# OctoWatchScheme2.net
KiCad netlist of a schematic drawn in EAGLE
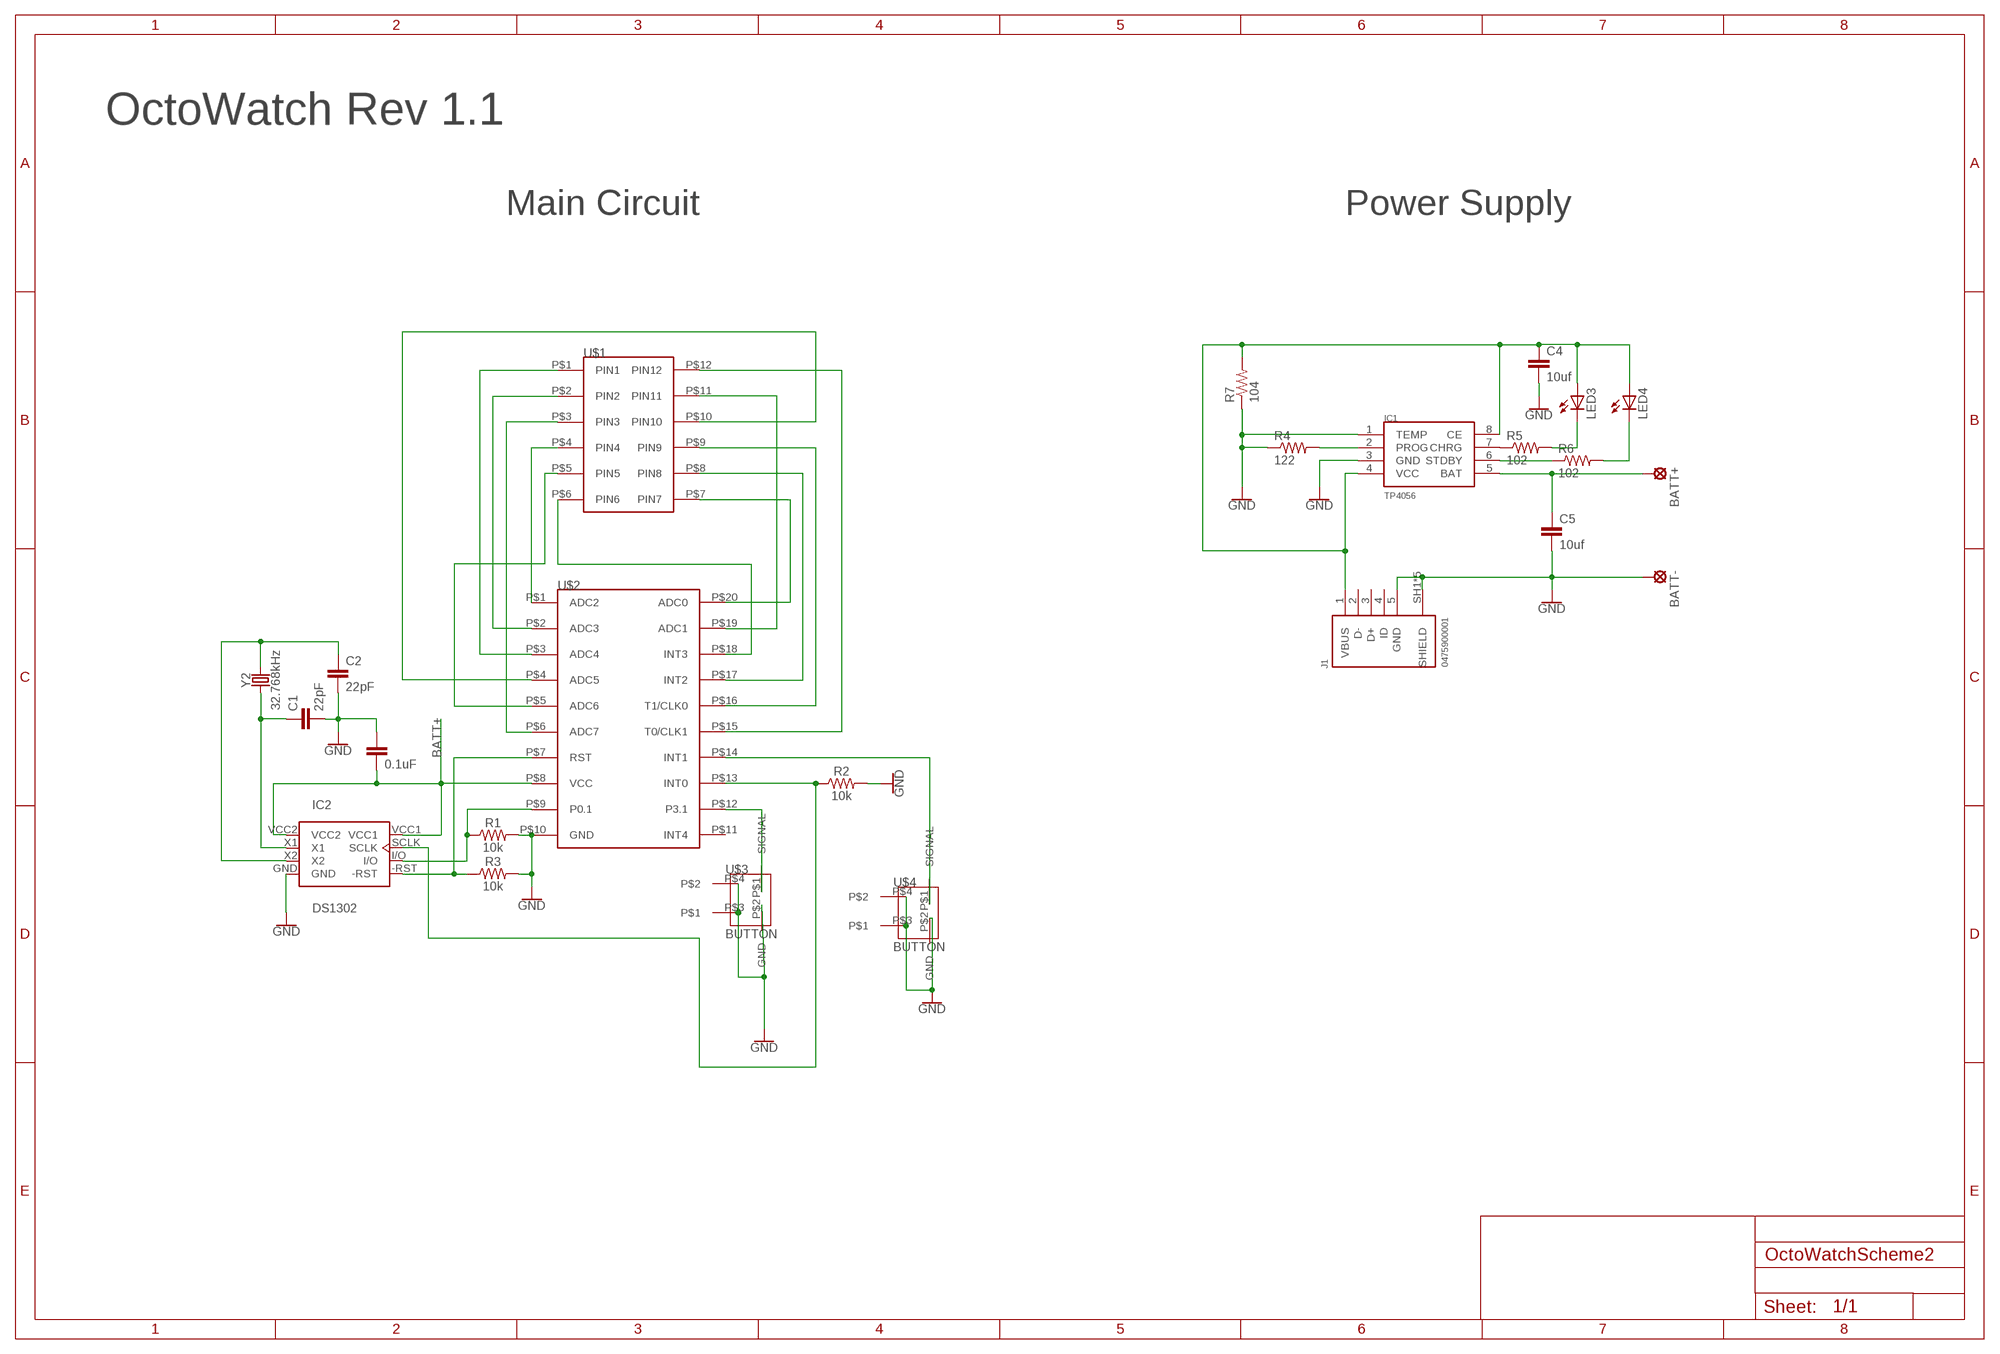
[diagram p0: schematic, sheet 1]

(export (version "E")
  (design (tool "Eeschema 10.0.6"))
  (components
    (comp (ref "BATT+")
      (value "LSP13")
      (footprint "eagle-import:LSP13")
      (libsource (lib "eagle-import") (part "LSP13"))
    )
    (comp (ref "BATT-")
      (value "LSP13")
      (footprint "eagle-import:LSP13")
      (libsource (lib "eagle-import") (part "LSP13"))
    )
    (comp (ref "C1")
      (value "22pF")
      (footprint "eagle-import:0402-TIGHT")
      (libsource (lib "eagle-import") (part "22PF-0402T-16V-10%"))
    )
    (comp (ref "C2")
      (value "22pF")
      (footprint "eagle-import:0402-TIGHT")
      (libsource (lib "eagle-import") (part "22PF-0402T-16V-10%"))
    )
    (comp (ref "C3")
      (value "0.1uF")
      (footprint "eagle-import:0402")
      (libsource (lib "eagle-import") (part "0.1UF-0402-6.3V-10%-X7R"))
    )
    (comp (ref "C4")
      (value "10uf")
      (footprint "eagle-import:C0805")
      (libsource (lib "eagle-import") (part "C-EUC0805"))
    )
    (comp (ref "C5")
      (value "10uf")
      (footprint "eagle-import:C0805")
      (libsource (lib "eagle-import") (part "C-EUC0805"))
    )
    (comp (ref "IC1")
      (value "TP4056")
      (footprint "eagle-import:SOP-8")
      (libsource (lib "eagle-import") (part "TP4056"))
    )
    (comp (ref "IC2")
      (value "DS1302")
      (footprint "eagle-import:DIL08")
      (libsource (lib "eagle-import") (part "DS1302"))
    )
    (comp (ref "J1")
      (value "0475900001")
      (footprint "eagle-import:0475900001")
      (fields
        (field (name "DIGIKEY_PARTNO") "WM17144TR-ND")
        (field (name "MANUFACTURER") "Molex")
        (field (name "CREATED_BY") "PCBLayout.com")
      )
      (libsource (lib "eagle-import") (part "0475900001"))
    )
    (comp (ref "LED3")
      (value "LEDCHIPLED_0603")
      (footprint "eagle-import:CHIPLED_0603")
      (libsource (lib "eagle-import") (part "LEDCHIPLED_0603"))
    )
    (comp (ref "LED4")
      (value "LEDCHIPLED_0603")
      (footprint "eagle-import:CHIPLED_0603")
      (libsource (lib "eagle-import") (part "LEDCHIPLED_0603"))
    )
    (comp (ref "R1")
      (value "10k")
      (footprint "eagle-import:0603")
      (libsource (lib "eagle-import") (part "10KOHM-0603-1/10W-1%"))
    )
    (comp (ref "R2")
      (value "10k")
      (footprint "eagle-import:0603")
      (libsource (lib "eagle-import") (part "10KOHM-0603-1/10W-1%"))
    )
    (comp (ref "R3")
      (value "10k")
      (footprint "eagle-import:0603")
      (libsource (lib "eagle-import") (part "10KOHM-0603-1/10W-1%"))
    )
    (comp (ref "R4")
      (value "122")
      (footprint "eagle-import:R0402")
      (libsource (lib "eagle-import") (part "rcl_334_R-US_R0402"))
    )
    (comp (ref "R5")
      (value "102")
      (footprint "eagle-import:R0402")
      (libsource (lib "eagle-import") (part "rcl_334_R-US_R0402"))
    )
    (comp (ref "R6")
      (value "102")
      (footprint "eagle-import:R0402")
      (libsource (lib "eagle-import") (part "rcl_334_R-US_R0402"))
    )
    (comp (ref "R7")
      (value "104")
      (footprint "eagle-import:R0805")
      (libsource (lib "eagle-import") (part "R-US_R0805"))
    )
    (comp (ref "U$1")
      (value "LED_SEGMENT")
      (footprint "eagle-import:LED_SEGMENT")
      (libsource (lib "eagle-import") (part "LED_SEGMENT"))
    )
    (comp (ref "U$2")
      (value "STC15F204AE")
      (footprint "eagle-import:STC15F204AE")
      (libsource (lib "eagle-import") (part "STC15F204AE"))
    )
    (comp (ref "U$3")
      (value "BUTTON")
      (footprint "eagle-import:BUTTON")
      (libsource (lib "eagle-import") (part "BUTTON"))
    )
    (comp (ref "U$4")
      (value "BUTTON")
      (footprint "eagle-import:BUTTON")
      (libsource (lib "eagle-import") (part "BUTTON"))
    )
    (comp (ref "Y2")
      (value "32.768kHz")
      (footprint "eagle-import:CRYSTAL-PTH-2X6-CYL")
      (libsource (lib "eagle-import") (part "CRYSTAL-32.768KHZPTH-2X6"))
    )
  )
  (nets
    (net (code "1") (name "/BATT+") (class "Default")
      (node (ref "C3") (pin "2") (pinfunction "2_2") (pintype "passive"))
      (node (ref "IC2") (pin "VCC1") (pinfunction "VCC1_VCC1") (pintype "power_in"))
      (node (ref "IC2") (pin "VCC2") (pinfunction "VCC2_VCC2") (pintype "power_in"))
      (node (ref "U$2") (pin "P$8") (pinfunction "VCC_P$8") (pintype "bidirectional"))
    )
    (net (code "2") (name "GND") (class "Default")
      (node (ref "BATT-") (pin "MP") (pinfunction "MP_MP") (pintype "passive"))
      (node (ref "C1") (pin "2") (pinfunction "2_2") (pintype "passive"))
      (node (ref "C2") (pin "2") (pinfunction "2_2") (pintype "passive"))
      (node (ref "C3") (pin "1") (pinfunction "1_1") (pintype "passive"))
      (node (ref "C4") (pin "2") (pinfunction "2_2") (pintype "passive"))
      (node (ref "C5") (pin "2") (pinfunction "2_2") (pintype "passive"))
      (node (ref "IC1") (pin "1") (pinfunction "TEMP_1") (pintype "bidirectional"))
      (node (ref "IC1") (pin "3") (pinfunction "GND_3") (pintype "bidirectional"))
      (node (ref "IC2") (pin "GND") (pinfunction "GND_GND") (pintype "passive"))
      (node (ref "J1") (pin "5") (pinfunction "GND_5") (pintype "passive"))
      (node (ref "J1") (pin "SH1") (pinfunction "SHIELD_SH1") (pintype "power_in"))
      (node (ref "J1") (pin "SH2") (pinfunction "SHIELD_SH2") (pintype "power_in"))
      (node (ref "J1") (pin "SH3") (pinfunction "SHIELD_SH3") (pintype "power_in"))
      (node (ref "J1") (pin "SH4") (pinfunction "SHIELD_SH4") (pintype "power_in"))
      (node (ref "J1") (pin "SH5") (pinfunction "SHIELD_SH5") (pintype "power_in"))
      (node (ref "R1") (pin "2") (pinfunction "2_2") (pintype "passive"))
      (node (ref "R2") (pin "2") (pinfunction "2_2") (pintype "passive"))
      (node (ref "R3") (pin "2") (pinfunction "2_2") (pintype "passive"))
      (node (ref "R4") (pin "1") (pinfunction "1_1") (pintype "passive"))
      (node (ref "R7") (pin "1") (pinfunction "1_1") (pintype "passive"))
      (node (ref "U$2") (pin "P$10") (pinfunction "GND_P$10") (pintype "bidirectional"))
      (node (ref "U$3") (pin "P$2") (pinfunction "GND_P$2") (pintype "bidirectional"))
      (node (ref "U$3") (pin "P$3") (pinfunction "P$1_P$3") (pintype "bidirectional"))
      (node (ref "U$3") (pin "P$4") (pinfunction "P$2_P$4") (pintype "bidirectional"))
      (node (ref "U$4") (pin "P$2") (pinfunction "GND_P$2") (pintype "bidirectional"))
      (node (ref "U$4") (pin "P$3") (pinfunction "P$1_P$3") (pintype "bidirectional"))
      (node (ref "U$4") (pin "P$4") (pinfunction "P$2_P$4") (pintype "bidirectional"))
    )
    (net (code "3") (name "Net-(C1-Pad1)") (class "Default")
      (node (ref "C1") (pin "1") (pinfunction "1_1") (pintype "passive"))
      (node (ref "IC2") (pin "X1") (pinfunction "X1_X1") (pintype "tri_state"))
      (node (ref "Y2") (pin "1") (pinfunction "1_1") (pintype "passive"))
    )
    (net (code "4") (name "Net-(C2-Pad1)") (class "Default")
      (node (ref "C2") (pin "1") (pinfunction "1_1") (pintype "passive"))
      (node (ref "IC2") (pin "X2") (pinfunction "X2_X2") (pintype "tri_state"))
      (node (ref "Y2") (pin "2") (pinfunction "2_2") (pintype "passive"))
    )
    (net (code "5") (name "Net-(IC1-BAT)") (class "Default")
      (node (ref "BATT+") (pin "MP") (pinfunction "MP_MP") (pintype "passive"))
      (node (ref "C5") (pin "1") (pinfunction "1_1") (pintype "passive"))
      (node (ref "IC1") (pin "5") (pinfunction "BAT_5") (pintype "bidirectional"))
    )
    (net (code "6") (name "Net-(IC1-CE)") (class "Default")
      (node (ref "C4") (pin "1") (pinfunction "1_1") (pintype "passive"))
      (node (ref "IC1") (pin "4") (pinfunction "VCC_4") (pintype "bidirectional"))
      (node (ref "IC1") (pin "8") (pinfunction "CE_8") (pintype "bidirectional"))
      (node (ref "J1") (pin "1") (pinfunction "VBUS_1") (pintype "passive"))
      (node (ref "LED3") (pin "A") (pinfunction "A_A") (pintype "passive"))
      (node (ref "LED4") (pin "A") (pinfunction "A_A") (pintype "passive"))
      (node (ref "R7") (pin "2") (pinfunction "2_2") (pintype "passive"))
    )
    (net (code "7") (name "Net-(IC1-CHRG)") (class "Default")
      (node (ref "IC1") (pin "7") (pinfunction "CHRG_7") (pintype "bidirectional"))
      (node (ref "R5") (pin "1") (pinfunction "1_1") (pintype "passive"))
    )
    (net (code "8") (name "Net-(IC1-PROG)") (class "Default")
      (node (ref "IC1") (pin "2") (pinfunction "PROG_2") (pintype "bidirectional"))
      (node (ref "R4") (pin "2") (pinfunction "2_2") (pintype "passive"))
    )
    (net (code "9") (name "Net-(IC1-STDBY)") (class "Default")
      (node (ref "IC1") (pin "6") (pinfunction "STDBY_6") (pintype "bidirectional"))
      (node (ref "R6") (pin "1") (pinfunction "1_1") (pintype "passive"))
    )
    (net (code "10") (name "Net-(LED3-PadC)") (class "Default")
      (node (ref "LED3") (pin "C") (pinfunction "C_C") (pintype "passive"))
      (node (ref "R5") (pin "2") (pinfunction "2_2") (pintype "passive"))
    )
    (net (code "11") (name "Net-(LED4-PadC)") (class "Default")
      (node (ref "LED4") (pin "C") (pinfunction "C_C") (pintype "passive"))
      (node (ref "R6") (pin "2") (pinfunction "2_2") (pintype "passive"))
    )
    (net (code "12") (name "Net-(U$1-PIN1)") (class "Default")
      (node (ref "U$1") (pin "P$1") (pinfunction "PIN1_P$1") (pintype "bidirectional"))
      (node (ref "U$2") (pin "P$3") (pinfunction "ADC4_P$3") (pintype "bidirectional"))
    )
    (net (code "13") (name "Net-(U$1-PIN2)") (class "Default")
      (node (ref "U$1") (pin "P$2") (pinfunction "PIN2_P$2") (pintype "bidirectional"))
      (node (ref "U$2") (pin "P$2") (pinfunction "ADC3_P$2") (pintype "bidirectional"))
    )
    (net (code "14") (name "Net-(U$1-PIN3)") (class "Default")
      (node (ref "U$1") (pin "P$3") (pinfunction "PIN3_P$3") (pintype "bidirectional"))
      (node (ref "U$2") (pin "P$6") (pinfunction "ADC7_P$6") (pintype "bidirectional"))
    )
    (net (code "15") (name "Net-(U$1-PIN4)") (class "Default")
      (node (ref "U$1") (pin "P$4") (pinfunction "PIN4_P$4") (pintype "bidirectional"))
      (node (ref "U$2") (pin "P$1") (pinfunction "ADC2_P$1") (pintype "bidirectional"))
    )
    (net (code "16") (name "Net-(U$1-PIN5)") (class "Default")
      (node (ref "U$1") (pin "P$5") (pinfunction "PIN5_P$5") (pintype "bidirectional"))
      (node (ref "U$2") (pin "P$5") (pinfunction "ADC6_P$5") (pintype "bidirectional"))
    )
    (net (code "17") (name "Net-(U$1-PIN6)") (class "Default")
      (node (ref "U$1") (pin "P$6") (pinfunction "PIN6_P$6") (pintype "bidirectional"))
      (node (ref "U$2") (pin "P$18") (pinfunction "INT3_P$18") (pintype "bidirectional"))
    )
    (net (code "18") (name "Net-(U$1-PIN7)") (class "Default")
      (node (ref "U$1") (pin "P$7") (pinfunction "PIN7_P$7") (pintype "bidirectional"))
      (node (ref "U$2") (pin "P$20") (pinfunction "ADC0_P$20") (pintype "bidirectional"))
    )
    (net (code "19") (name "Net-(U$1-PIN8)") (class "Default")
      (node (ref "U$1") (pin "P$8") (pinfunction "PIN8_P$8") (pintype "bidirectional"))
      (node (ref "U$2") (pin "P$17") (pinfunction "INT2_P$17") (pintype "bidirectional"))
    )
    (net (code "20") (name "Net-(U$1-PIN9)") (class "Default")
      (node (ref "U$1") (pin "P$9") (pinfunction "PIN9_P$9") (pintype "bidirectional"))
      (node (ref "U$2") (pin "P$16") (pinfunction "T1/CLK0_P$16") (pintype "bidirectional"))
    )
    (net (code "21") (name "Net-(U$1-PIN10)") (class "Default")
      (node (ref "U$1") (pin "P$10") (pinfunction "PIN10_P$10") (pintype "bidirectional"))
      (node (ref "U$2") (pin "P$4") (pinfunction "ADC5_P$4") (pintype "bidirectional"))
    )
    (net (code "22") (name "Net-(U$1-PIN11)") (class "Default")
      (node (ref "U$1") (pin "P$11") (pinfunction "PIN11_P$11") (pintype "bidirectional"))
      (node (ref "U$2") (pin "P$19") (pinfunction "ADC1_P$19") (pintype "bidirectional"))
    )
    (net (code "23") (name "Net-(U$1-PIN12)") (class "Default")
      (node (ref "U$1") (pin "P$12") (pinfunction "PIN12_P$12") (pintype "bidirectional"))
      (node (ref "U$2") (pin "P$15") (pinfunction "T0/CLK1_P$15") (pintype "bidirectional"))
    )
    (net (code "24") (name "Net-(U$2-INT0)") (class "Default")
      (node (ref "IC2") (pin "SCLK") (pinfunction "SCLK_SCLK") (pintype "tri_state"))
      (node (ref "R2") (pin "1") (pinfunction "1_1") (pintype "passive"))
      (node (ref "U$2") (pin "P$13") (pinfunction "INT0_P$13") (pintype "bidirectional"))
    )
    (net (code "25") (name "Net-(U$2-INT1)") (class "Default")
      (node (ref "U$2") (pin "P$14") (pinfunction "INT1_P$14") (pintype "bidirectional"))
      (node (ref "U$4") (pin "P$1") (pinfunction "SIGNAL_P$1") (pintype "bidirectional"))
    )
    (net (code "26") (name "Net-(U$2-P0.1)") (class "Default")
      (node (ref "IC2") (pin "I/O") (pinfunction "I/O_I/O") (pintype "bidirectional"))
      (node (ref "R1") (pin "1") (pinfunction "1_1") (pintype "passive"))
      (node (ref "U$2") (pin "P$9") (pinfunction "P0.1_P$9") (pintype "bidirectional"))
    )
    (net (code "27") (name "Net-(U$2-P3.1)") (class "Default")
      (node (ref "U$2") (pin "P$12") (pinfunction "P3.1_P$12") (pintype "bidirectional"))
      (node (ref "U$3") (pin "P$1") (pinfunction "SIGNAL_P$1") (pintype "bidirectional"))
    )
    (net (code "28") (name "Net-(U$2-RST)") (class "Default")
      (node (ref "IC2") (pin "-RST") (pinfunction "-RST_-RST") (pintype "bidirectional"))
      (node (ref "R3") (pin "1") (pinfunction "1_1") (pintype "passive"))
      (node (ref "U$2") (pin "P$7") (pinfunction "RST_P$7") (pintype "bidirectional"))
    )
    (net (code "29") (name "unconnected-(J1-D+-Pad3)") (class "Default")
      (node (ref "J1") (pin "3") (pinfunction "D+_3") (pintype "passive"))
    )
    (net (code "30") (name "unconnected-(J1-D--Pad2)") (class "Default")
      (node (ref "J1") (pin "2") (pinfunction "D-_2") (pintype "passive"))
    )
    (net (code "31") (name "unconnected-(J1-ID-Pad4)") (class "Default")
      (node (ref "J1") (pin "4") (pinfunction "ID_4") (pintype "passive"))
    )
    (net (code "32") (name "unconnected-(U$2-INT4-PadP$11)") (class "Default")
      (node (ref "U$2") (pin "P$11") (pinfunction "INT4_P$11") (pintype "bidirectional"))
    )
  )
)
